# Volta-Interface-SCH_SH2__01.net
KiCad netlist of a schematic drawn in Altium Designer
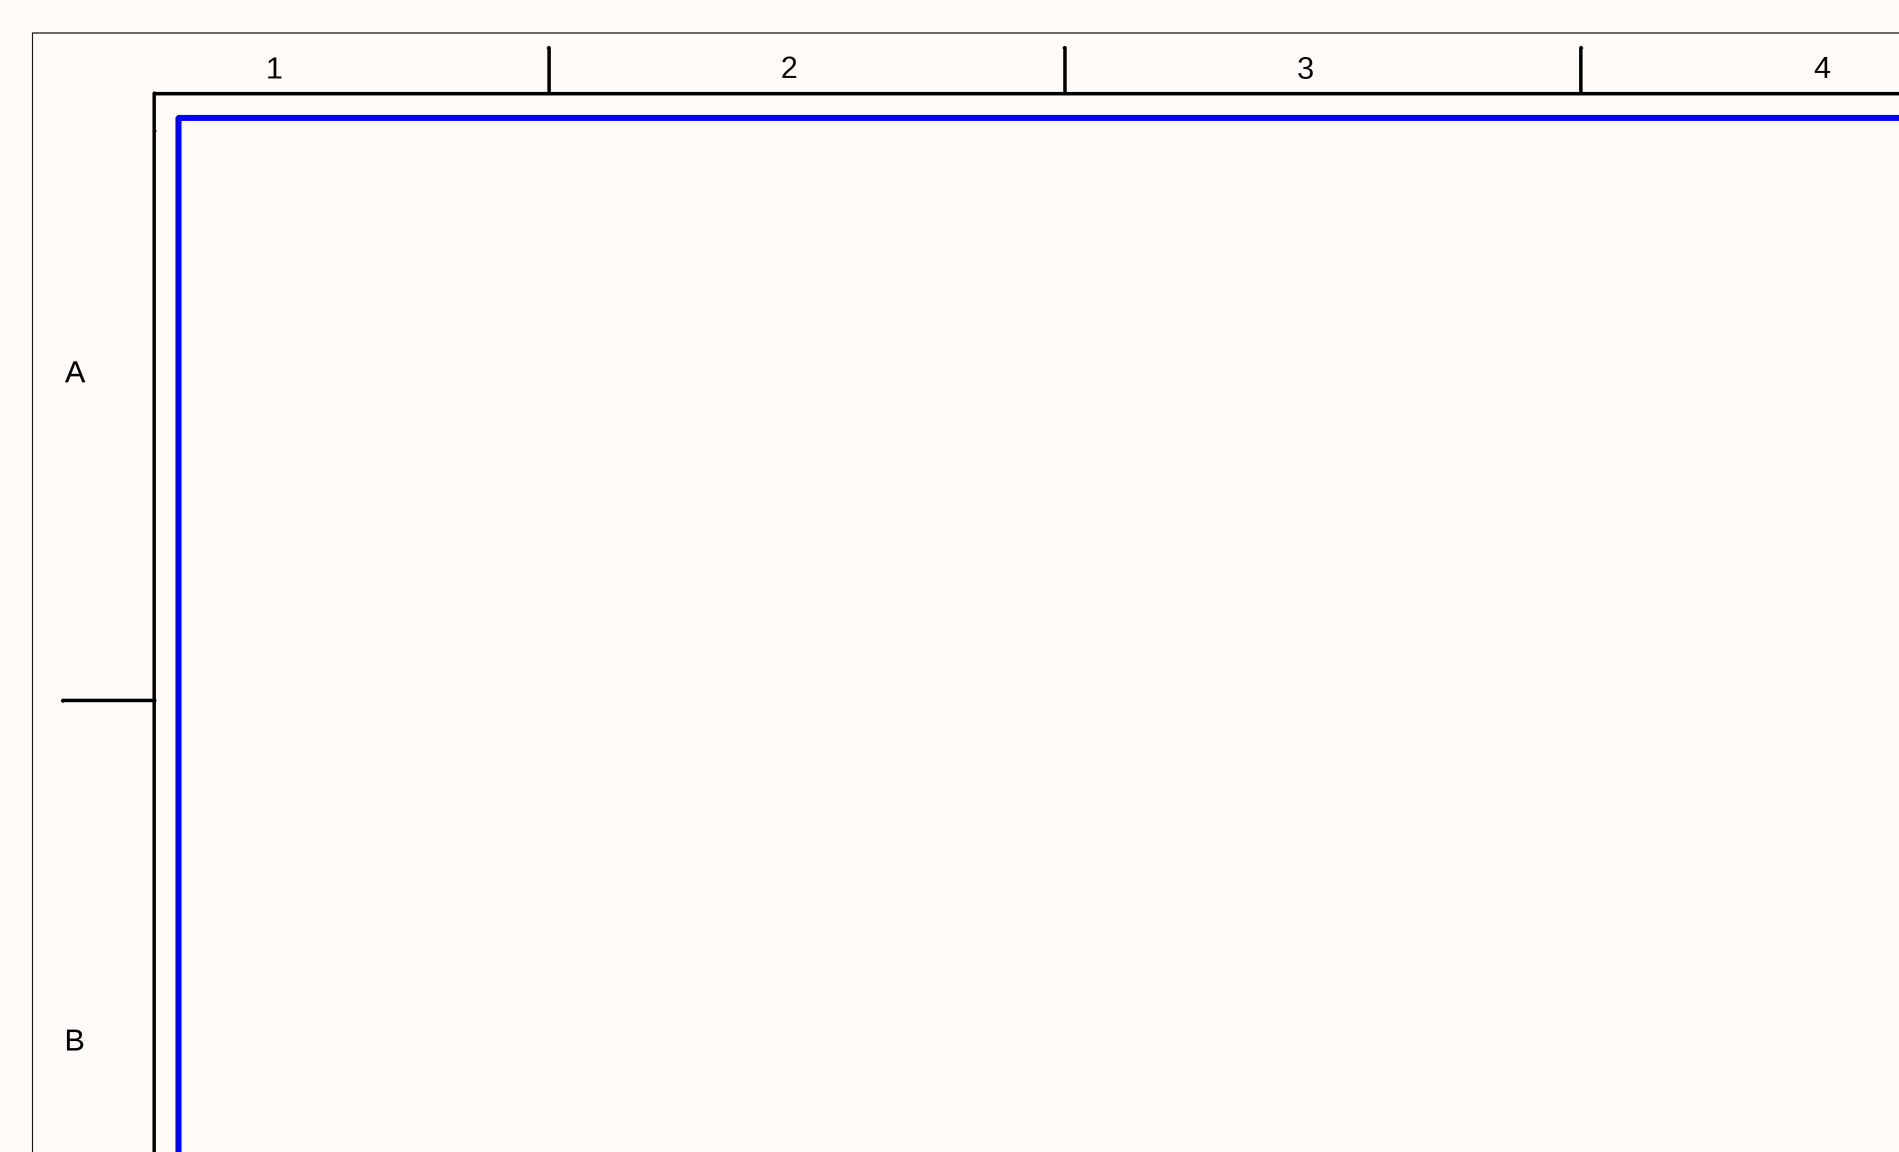
[diagram p0: Volta-Interface-SCH_SH2_(01).SchDoc, top left]
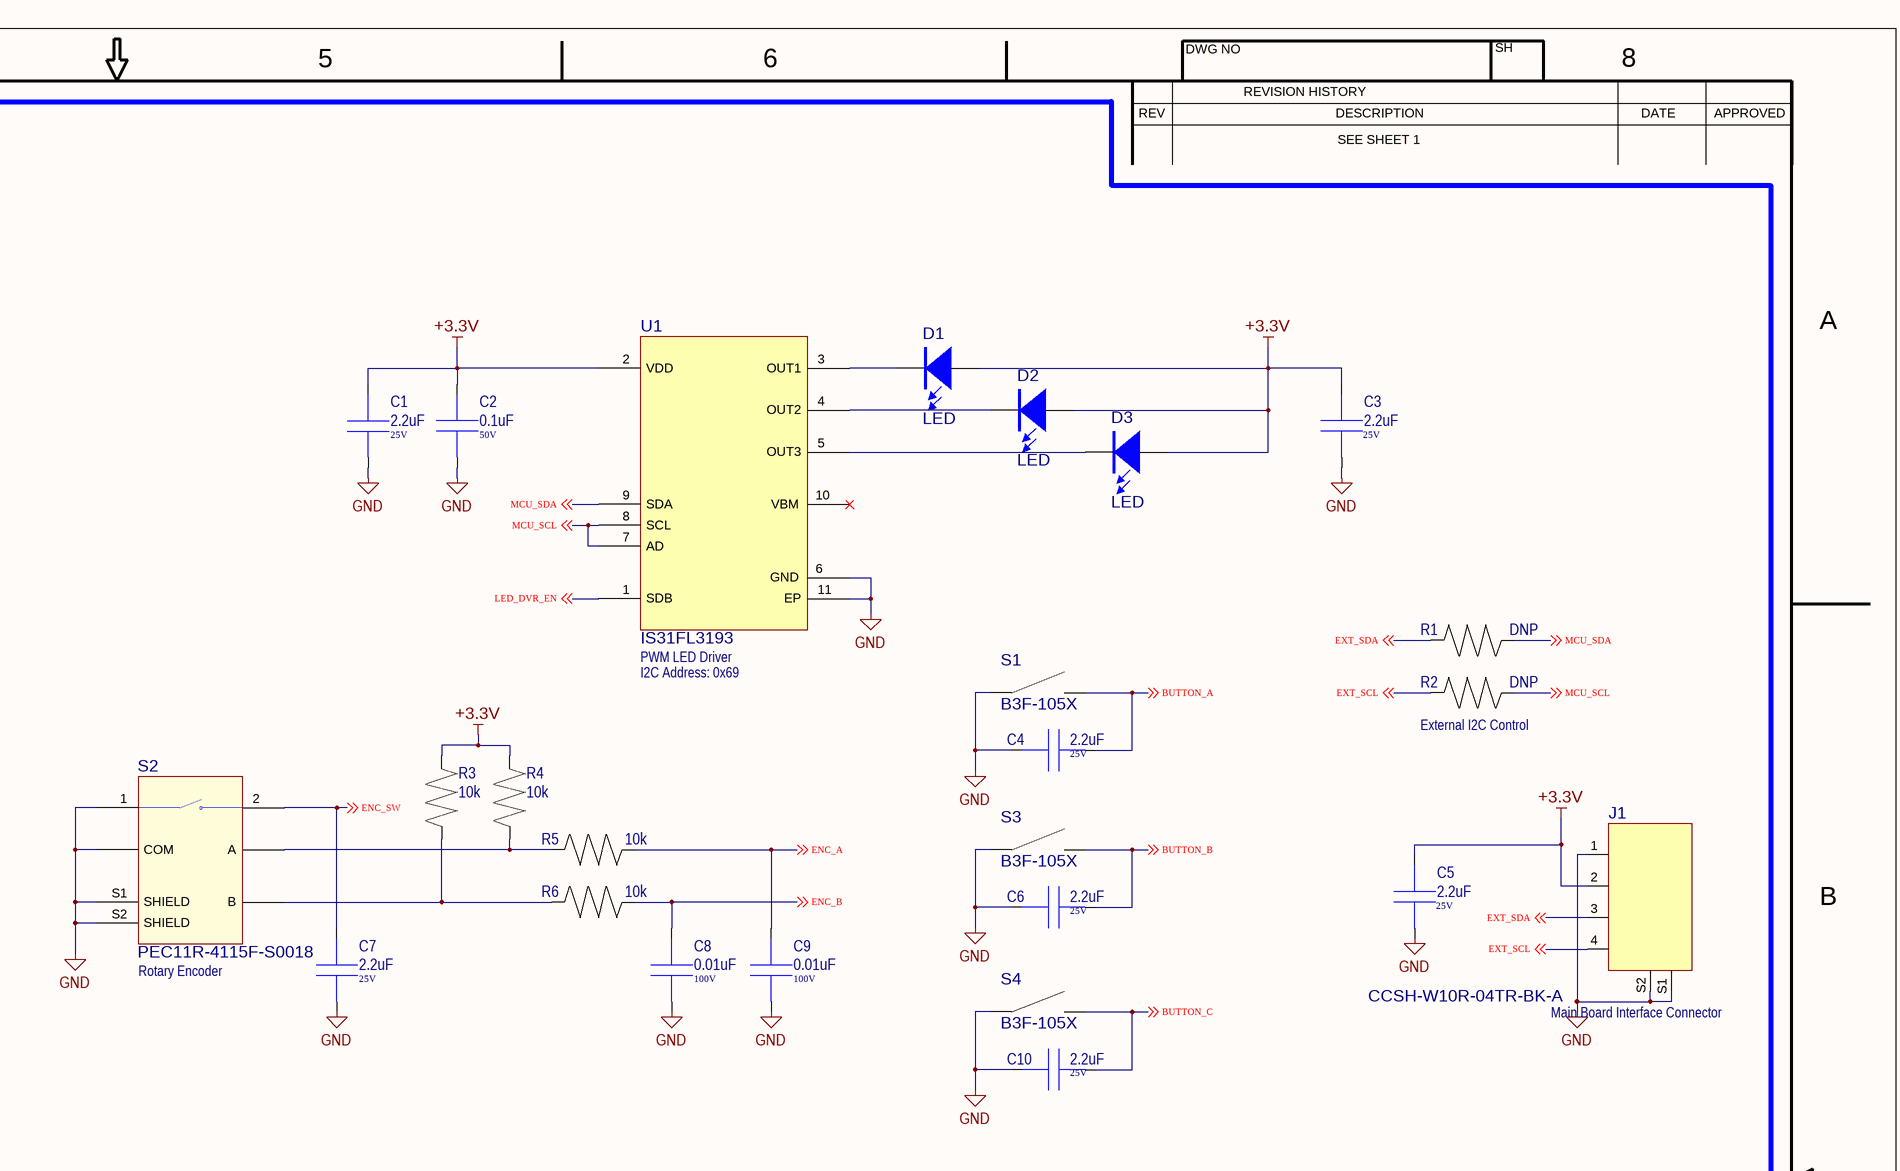
[diagram p1: Volta-Interface-SCH_SH2_(01).SchDoc, top right]
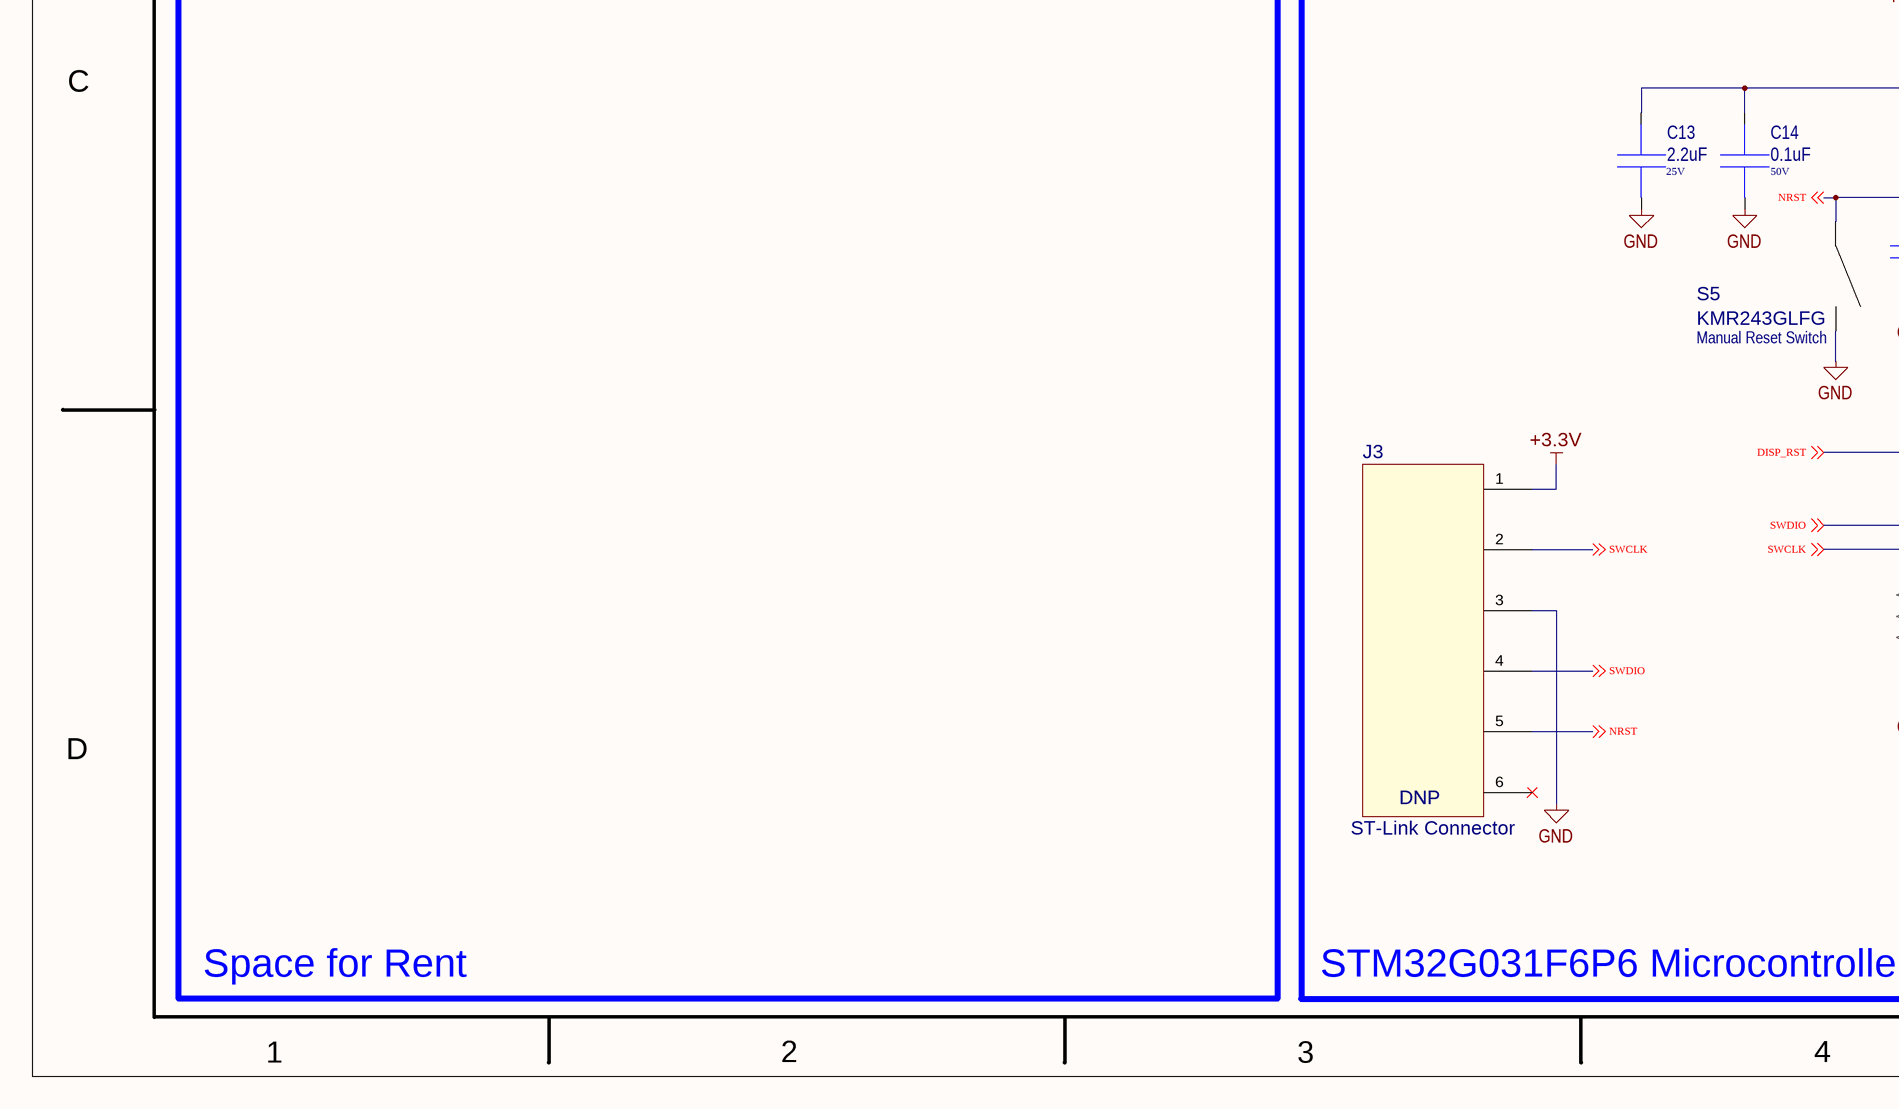
[diagram p2: Volta-Interface-SCH_SH2_(01).SchDoc, bottom left]
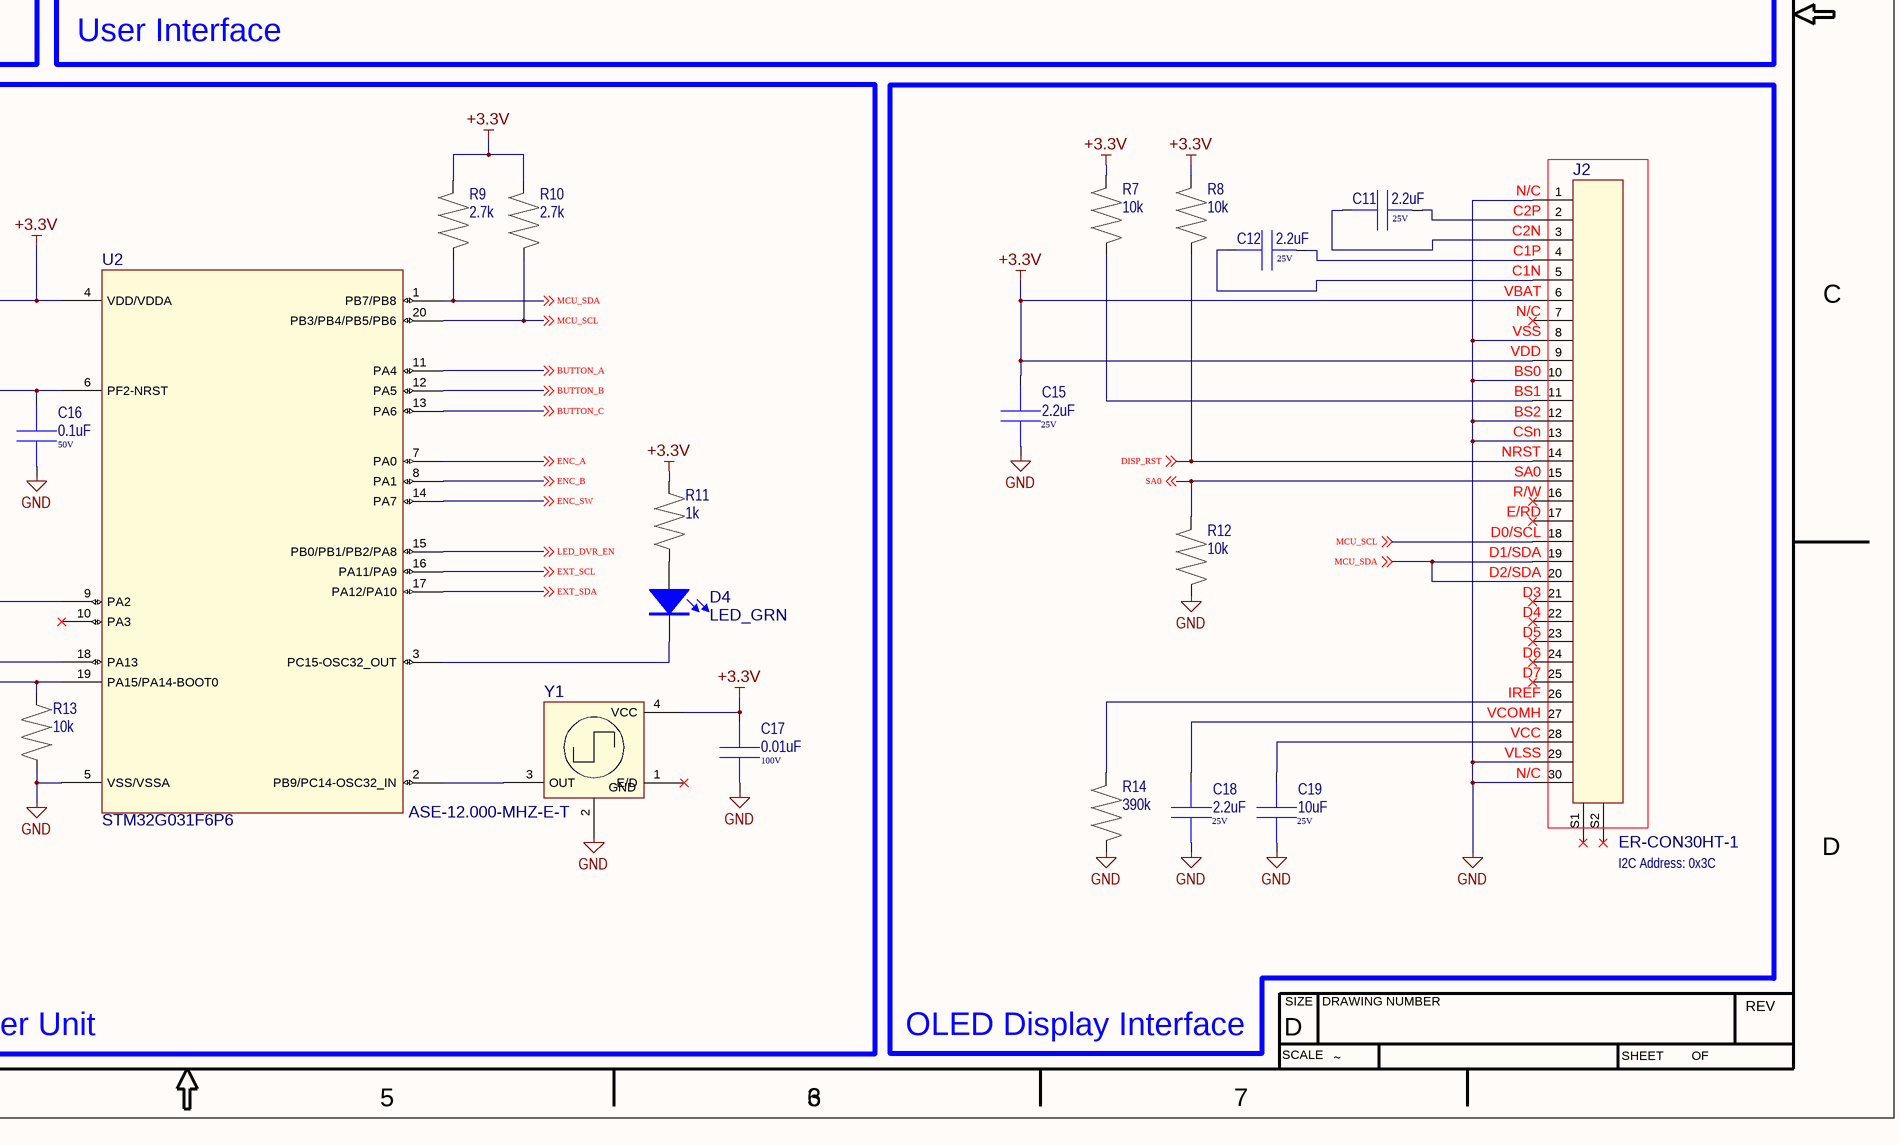
[diagram p3: Volta-Interface-SCH_SH2_(01).SchDoc, bottom right]

(export (version "E")
  (design (tool "Eeschema 10.0.6"))
  (components
    (comp (ref "C1")
      (value "2.2uF")
      (footprint "0402")
      (description "Multilayer Ceramic Capacitors MLCC - SMD/SMT 2.2UF 25V 10% 0402")
      (fields
        (field (name "PART NUMBER") "GRM155R61E225KE11D")
        (field (name "MANUFACTURER") "Murata Electronics")
        (field (name "VOLTAGE") "25V")
      )
      (libsource (lib "CAPACITORS") (part "CAP"))
    )
    (comp (ref "C2")
      (value "0.1uF")
      (footprint "0402")
      (description "CAP CER 0.1UF 50V X7R 0402")
      (fields
        (field (name "PART NUMBER") "UMK105B7104KVHF")
        (field (name "MANUFACTURER") "Taiyo Yuden")
        (field (name "VOLTAGE") "50V")
      )
      (libsource (lib "CAPACITORS") (part "CAP"))
    )
    (comp (ref "C3")
      (value "2.2uF")
      (footprint "0402")
      (description "Multilayer Ceramic Capacitors MLCC - SMD/SMT 2.2UF 25V 10% 0402")
      (fields
        (field (name "PART NUMBER") "GRM155R61E225KE11D")
        (field (name "MANUFACTURER") "Murata Electronics")
        (field (name "VOLTAGE") "25V")
      )
      (libsource (lib "CAPACITORS") (part "CAP"))
    )
    (comp (ref "C4")
      (value "2.2uF")
      (footprint "0402")
      (description "Multilayer Ceramic Capacitors MLCC - SMD/SMT 2.2UF 25V 10% 0402")
      (fields
        (field (name "PART NUMBER") "GRM155R61E225KE11D")
        (field (name "MANUFACTURER") "Murata Electronics")
        (field (name "VOLTAGE") "25V")
      )
      (libsource (lib "CAPACITORS") (part "CAP"))
    )
    (comp (ref "C5")
      (value "2.2uF")
      (footprint "0402")
      (description "Multilayer Ceramic Capacitors MLCC - SMD/SMT 2.2UF 25V 10% 0402")
      (fields
        (field (name "PART NUMBER") "GRM155R61E225KE11D")
        (field (name "MANUFACTURER") "Murata Electronics")
        (field (name "VOLTAGE") "25V")
      )
      (libsource (lib "CAPACITORS") (part "CAP"))
    )
    (comp (ref "C6")
      (value "2.2uF")
      (footprint "0402")
      (description "Multilayer Ceramic Capacitors MLCC - SMD/SMT 2.2UF 25V 10% 0402")
      (fields
        (field (name "PART NUMBER") "GRM155R61E225KE11D")
        (field (name "MANUFACTURER") "Murata Electronics")
        (field (name "VOLTAGE") "25V")
      )
      (libsource (lib "CAPACITORS") (part "CAP"))
    )
    (comp (ref "C7")
      (value "2.2uF")
      (footprint "0402")
      (description "Multilayer Ceramic Capacitors MLCC - SMD/SMT 2.2UF 25V 10% 0402")
      (fields
        (field (name "PART NUMBER") "GRM155R61E225KE11D")
        (field (name "MANUFACTURER") "Murata Electronics")
        (field (name "VOLTAGE") "25V")
      )
      (libsource (lib "CAPACITORS") (part "CAP"))
    )
    (comp (ref "C8")
      (value "0.01uF")
      (footprint "0402")
      (description "CAP CER 0.01UF 100V X7R 0402")
      (fields
        (field (name "PART NUMBER") "HMR105B7103MV-F")
        (field (name "MANUFACTURER") "Taiyo Yuden")
        (field (name "VOLTAGE") "100V")
      )
      (libsource (lib "CAPACITORS") (part "CAP"))
    )
    (comp (ref "C9")
      (value "0.01uF")
      (footprint "0402")
      (description "CAP CER 0.01UF 100V X7R 0402")
      (fields
        (field (name "PART NUMBER") "HMR105B7103MV-F")
        (field (name "MANUFACTURER") "Taiyo Yuden")
        (field (name "VOLTAGE") "100V")
      )
      (libsource (lib "CAPACITORS") (part "CAP"))
    )
    (comp (ref "C10")
      (value "2.2uF")
      (footprint "0402")
      (description "Multilayer Ceramic Capacitors MLCC - SMD/SMT 2.2UF 25V 10% 0402")
      (fields
        (field (name "PART NUMBER") "GRM155R61E225KE11D")
        (field (name "MANUFACTURER") "Murata Electronics")
        (field (name "VOLTAGE") "25V")
      )
      (libsource (lib "CAPACITORS") (part "CAP"))
    )
    (comp (ref "C11")
      (value "2.2uF")
      (footprint "0402")
      (description "CAP CER 10UF 10V X6S 0603")
      (fields
        (field (name "PART NUMBER") "GRM188C81A106MA73D")
        (field (name "MANUFACTURER") "Murata Electronics")
        (field (name "VOLTAGE") "25V")
      )
      (libsource (lib "CAPACITORS") (part "CAP"))
    )
    (comp (ref "C12")
      (value "2.2uF")
      (footprint "0402")
      (description "CAP CER 10UF 10V X6S 0603")
      (fields
        (field (name "PART NUMBER") "GRM188C81A106MA73D")
        (field (name "MANUFACTURER") "Murata Electronics")
        (field (name "VOLTAGE") "25V")
      )
      (libsource (lib "CAPACITORS") (part "CAP"))
    )
    (comp (ref "C13")
      (value "2.2uF")
      (footprint "0402")
      (description "Multilayer Ceramic Capacitors MLCC - SMD/SMT 2.2UF 25V 10% 0402")
      (fields
        (field (name "PART NUMBER") "GRM155R61E225KE11D")
        (field (name "MANUFACTURER") "Murata Electronics")
        (field (name "VOLTAGE") "25V")
      )
      (libsource (lib "CAPACITORS") (part "CAP"))
    )
    (comp (ref "C14")
      (value "0.1uF")
      (footprint "0402")
      (description "CAP CER 0.1UF 50V X7R 0402")
      (fields
        (field (name "PART NUMBER") "UMK105B7104KVHF")
        (field (name "MANUFACTURER") "Taiyo Yuden")
        (field (name "VOLTAGE") "50V")
      )
      (libsource (lib "CAPACITORS") (part "CAP"))
    )
    (comp (ref "C15")
      (value "2.2uF")
      (footprint "0402")
      (description "CAP CER 10UF 10V X6S 0603")
      (fields
        (field (name "PART NUMBER") "GRM188C81A106MA73D")
        (field (name "MANUFACTURER") "Murata Electronics")
        (field (name "VOLTAGE") "25V")
      )
      (libsource (lib "CAPACITORS") (part "CAP"))
    )
    (comp (ref "C16")
      (value "0.1uF")
      (footprint "0402")
      (description "CAP CER 0.1UF 50V X7R 0402")
      (fields
        (field (name "PART NUMBER") "UMK105B7104KVHF")
        (field (name "MANUFACTURER") "Taiyo Yuden")
        (field (name "VOLTAGE") "50V")
      )
      (libsource (lib "CAPACITORS") (part "CAP"))
    )
    (comp (ref "C17")
      (value "0.01uF")
      (footprint "0402")
      (description "CAP CER 0.01UF 100V X7R 0402")
      (fields
        (field (name "PART NUMBER") "HMR105B7103MV-F")
        (field (name "MANUFACTURER") "Taiyo Yuden")
        (field (name "VOLTAGE") "100V")
      )
      (libsource (lib "CAPACITORS") (part "CAP"))
    )
    (comp (ref "C18")
      (value "2.2uF")
      (footprint "0402")
      (description "CAP CER 10UF 10V X6S 0603")
      (fields
        (field (name "PART NUMBER") "GRM188C81A106MA73D")
        (field (name "MANUFACTURER") "Murata Electronics")
        (field (name "VOLTAGE") "25V")
      )
      (libsource (lib "CAPACITORS") (part "CAP"))
    )
    (comp (ref "C19")
      (value "10uF")
      (footprint "0402")
      (description "CAP CER 10UF 10V X6S 0603")
      (fields
        (field (name "PART NUMBER") "GRM188C81A106MA73D")
        (field (name "MANUFACTURER") "Murata Electronics")
        (field (name "VOLTAGE") "25V")
      )
      (libsource (lib "CAPACITORS") (part "CAP"))
    )
    (comp (ref "D1") (value "LED") (footprint "1206_LED") (libsource (lib "SEMICONDUCTORS") (part "LED")))
    (comp (ref "D2") (value "LED") (footprint "1206_LED") (libsource (lib "SEMICONDUCTORS") (part "LED")))
    (comp (ref "D3") (value "LED") (footprint "1206_LED") (libsource (lib "SEMICONDUCTORS") (part "LED")))
    (comp (ref "D4")
      (value "LED_GRN")
      (footprint "0603_LED_Red")
      (description "Standard LEDs - SMD HE Red 645 nm Water Clear")
      (fields (field (name "PART NUMBER") "SM0603HCL") (field (name "MANUFACTURER") "Bivar"))
      (libsource (lib "SEMICONDUCTORS") (part "LED_Red"))
    )
    (comp (ref "J1")
      (value "CCSH-W10R-04TR-BK-A")
      (footprint "PCBComponent_1")
      (fields (field (name "MANUFACTURER") "JST"))
      (libsource (lib "CCSH-W10R-04TR-BK-A") (part "CCSH-W10R-04TR-BK-A"))
    )
    (comp (ref "J2")
      (value "ER-CON30HT-1")
      (footprint "ER-CON30HT-1")
      (description "30 PINS 0.5 PITCH SMD TOP CONTACT CONN")
      (fields (field (name "MANUFACTURER") "EastRising Technology"))
      (libsource (lib "ER-CON30HT-1") (part "ER-CON30HT-1"))
    )
    (comp (ref "J3")
      (value "DNP")
      (footprint "801-93-006-10-012000")
      (description "CONN SOCKET STRIP LOPRO 6POS")
      (fields (field (name "MANUFACTURER") "Mill-Max") (field (name "PART NUMBER") "801-93-006-10-012000"))
      (libsource (lib "Connectors") (part "801-93-006-10-012000"))
    )
    (comp (ref "R1")
      (value "DNP")
      (footprint "0402")
      (description "Thick Film Resistors - SMD 1/16watt 0ohm Commercial Use")
      (fields (field (name "PART NUMBER") "CRCW04020000Z0EDC") (field (name "MANUFACTURER") "Vishay / Dale"))
      (libsource (lib "RESISTORS") (part "RES"))
    )
    (comp (ref "R2")
      (value "DNP")
      (footprint "0402")
      (description "Thick Film Resistors - SMD 1/16watt 0ohm Commercial Use")
      (fields (field (name "PART NUMBER") "CRCW04020000Z0EDC") (field (name "MANUFACTURER") "Vishay / Dale"))
      (libsource (lib "RESISTORS") (part "RES"))
    )
    (comp (ref "R3")
      (value "10k")
      (footprint "0402")
      (description "Thick Film Resistors - SMD 10K OHM 1%")
      (fields (field (name "PART NUMBER") "CR0402-FX-1002GLF") (field (name "MANUFACTURER") "Bourns"))
      (libsource (lib "RESISTORS") (part "RES"))
    )
    (comp (ref "R4")
      (value "10k")
      (footprint "0402")
      (description "Thick Film Resistors - SMD 10K OHM 1%")
      (fields (field (name "PART NUMBER") "CR0402-FX-1002GLF") (field (name "MANUFACTURER") "Bourns"))
      (libsource (lib "RESISTORS") (part "RES"))
    )
    (comp (ref "R5")
      (value "10k")
      (footprint "0402")
      (description "Thick Film Resistors - SMD 10K OHM 1%")
      (fields (field (name "PART NUMBER") "CR0402-FX-1002GLF") (field (name "MANUFACTURER") "Bourns"))
      (libsource (lib "RESISTORS") (part "RES"))
    )
    (comp (ref "R6")
      (value "10k")
      (footprint "0402")
      (description "Thick Film Resistors - SMD 10K OHM 1%")
      (fields (field (name "PART NUMBER") "CR0402-FX-1002GLF") (field (name "MANUFACTURER") "Bourns"))
      (libsource (lib "RESISTORS") (part "RES"))
    )
    (comp (ref "R7")
      (value "10k")
      (footprint "0402")
      (description "Thick Film Resistors - SMD 0603 5.1Kohm 5% High Voltage")
      (fields (field (name "PART NUMBER") "KTR03EZPJ512") (field (name "MANUFACTURER") "ROHM Semiconductor"))
      (libsource (lib "RESISTORS") (part "RES"))
    )
    (comp (ref "R8")
      (value "10k")
      (footprint "0402")
      (description "Thick Film Resistors - SMD 0603 5.1Kohm 5% High Voltage")
      (fields (field (name "PART NUMBER") "KTR03EZPJ512") (field (name "MANUFACTURER") "ROHM Semiconductor"))
      (libsource (lib "RESISTORS") (part "RES"))
    )
    (comp (ref "R9")
      (value "2.7k")
      (footprint "0402")
      (description "Thick Film Resistors - SMD 0402 2.7Kohms 1% AEC-Q200")
      (fields (field (name "PART NUMBER") "ERJ-2RKF2701X") (field (name "MANUFACTURER") "Panasonic"))
      (libsource (lib "RESISTORS") (part "RES"))
    )
    (comp (ref "R10")
      (value "2.7k")
      (footprint "0402")
      (description "Thick Film Resistors - SMD 0402 2.7Kohms 1% AEC-Q200")
      (fields (field (name "PART NUMBER") "ERJ-2RKF2701X") (field (name "MANUFACTURER") "Panasonic"))
      (libsource (lib "RESISTORS") (part "RES"))
    )
    (comp (ref "R11")
      (value "1k")
      (footprint "0402")
      (description "Thick Film Resistors - SMD ResA 0402 1k 1% 63mW TC100")
      (fields (field (name "PART NUMBER") "CR0402AFX-1001GLF") (field (name "MANUFACTURER") "Bourns"))
      (libsource (lib "RESISTORS") (part "RES"))
    )
    (comp (ref "R12")
      (value "10k")
      (footprint "0402")
      (description "Thick Film Resistors - SMD 0603 5.1Kohm 5% High Voltage")
      (fields (field (name "PART NUMBER") "KTR03EZPJ512") (field (name "MANUFACTURER") "ROHM Semiconductor"))
      (libsource (lib "RESISTORS") (part "RES"))
    )
    (comp (ref "R13")
      (value "10k")
      (footprint "0402")
      (description "Thick Film Resistors - SMD 10K OHM 1%")
      (fields (field (name "PART NUMBER") "CR0402-FX-1002GLF") (field (name "MANUFACTURER") "Bourns"))
      (libsource (lib "RESISTORS") (part "RES"))
    )
    (comp (ref "R14")
      (value "390k")
      (footprint "0402")
      (description "Thick Film Resistors - SMD 0603 5.1Kohm 5% High Voltage")
      (fields (field (name "PART NUMBER") "KTR03EZPJ512") (field (name "MANUFACTURER") "ROHM Semiconductor"))
      (libsource (lib "RESISTORS") (part "RES"))
    )
    (comp (ref "S1")
      (value "B3F-105X")
      (footprint "B3F-105X")
      (description "SWITCH TACTILE SPST-NO 0.05A 24V")
      (fields (field (name "MANUFACTURER") "Omron Electronics Inc-EMC Div"))
      (libsource (lib "B3F-105X") (part "B3F-105X"))
    )
    (comp (ref "S2")
      (value "PEC11R-4115F-S0018")
      (footprint "PEC11R-4xxxF-Sxxxx")
      (description "ROTARY ENCODER MECHANICAL XXPPR")
      (fields (field (name "MANUFACTURER") "Bourns"))
      (libsource (lib "PEC11R-4xxxF-Sxxxx") (part "PEC11R-4xxxF-Sxxxx"))
    )
    (comp (ref "S3")
      (value "B3F-105X")
      (footprint "B3F-105X")
      (description "SWITCH TACTILE SPST-NO 0.05A 24V")
      (fields (field (name "MANUFACTURER") "Omron Electronics Inc-EMC Div"))
      (libsource (lib "B3F-105X") (part "B3F-105X"))
    )
    (comp (ref "S4")
      (value "B3F-105X")
      (footprint "B3F-105X")
      (description "SWITCH TACTILE SPST-NO 0.05A 24V")
      (fields (field (name "MANUFACTURER") "Omron Electronics Inc-EMC Div"))
      (libsource (lib "B3F-105X") (part "B3F-105X"))
    )
    (comp (ref "S5")
      (value "KMR243GLFG")
      (footprint "KMR 2 Series")
      (description "Tactile Switch SPST-NO Top Actuated Surface Mount")
      (fields (field (name "MANUFACTURER") "C&K") (field (name "PART NUMBER") "KMR243GFLG"))
      (libsource (lib "KMR2 Series") (part "KMR 2 Series"))
    )
    (comp (ref "U1")
      (value "IS31FL3193")
      (footprint "DFN-10")
      (description "IC LED DRIVER LINEAR 42MA 10DFN")
      (fields
        (field (name "MANUFACTURER") "Lumissil Microsystems")
        (field (name "PART NUMBER") "IS31FL3193-DLS2-TR")
      )
      (libsource (lib "IS31FL3193") (part "IS31FL3193"))
    )
    (comp (ref "U2")
      (value "STM32G031F6P6")
      (footprint "TSSOP-20")
      (description "IC MCU 32BIT 32KB FLASH 20TSSOP")
      (fields (field (name "MANUFACTURER") "STMicroelectronics"))
      (libsource (lib "STM32G031Fxxx") (part "STM32G031F6P6"))
    )
    (comp (ref "Y1")
      (value "ASE-12.000-MHZ-E-T")
      (footprint "ASE-XXXXX-X-X-X")
      (description "OSC XO 12.000MHZ CMOS SMD")
      (fields (field (name "MANUFACTURER") "Abracon"))
      (libsource (lib "Oscillators") (part "ASE-XXXXX-MHZ-X-X"))
    )
  )
  (nets
    (net (code "1") (name "+3.3V") (class "Default")
      (node (ref "C1") (pin "2") (pinfunction "2_2") (pintype "passive"))
      (node (ref "C13") (pin "2") (pinfunction "2_2") (pintype "passive"))
      (node (ref "C14") (pin "2") (pinfunction "2_2") (pintype "passive"))
      (node (ref "C15") (pin "2") (pinfunction "2_2") (pintype "passive"))
      (node (ref "C17") (pin "2") (pinfunction "2_2") (pintype "passive"))
      (node (ref "C2") (pin "2") (pinfunction "2_2") (pintype "passive"))
      (node (ref "C3") (pin "2") (pinfunction "2_2") (pintype "passive"))
      (node (ref "C5") (pin "2") (pinfunction "2_2") (pintype "passive"))
      (node (ref "D1") (pin "1") (pinfunction "A_1") (pintype "passive"))
      (node (ref "D2") (pin "1") (pinfunction "A_1") (pintype "passive"))
      (node (ref "D3") (pin "1") (pinfunction "A_1") (pintype "passive"))
      (node (ref "J1") (pin "2") (pinfunction "2_2") (pintype "passive"))
      (node (ref "J2") (pin "6") (pinfunction "6_6") (pintype "passive"))
      (node (ref "J2") (pin "9") (pinfunction "9_9") (pintype "passive"))
      (node (ref "J3") (pin "1") (pinfunction "1_1") (pintype "passive"))
      (node (ref "R10") (pin "2") (pinfunction "2_2") (pintype "passive"))
      (node (ref "R11") (pin "2") (pinfunction "2_2") (pintype "passive"))
      (node (ref "R3") (pin "1") (pinfunction "1_1") (pintype "passive"))
      (node (ref "R4") (pin "1") (pinfunction "1_1") (pintype "passive"))
      (node (ref "R7") (pin "2") (pinfunction "2_2") (pintype "passive"))
      (node (ref "R8") (pin "2") (pinfunction "2_2") (pintype "passive"))
      (node (ref "R9") (pin "2") (pinfunction "2_2") (pintype "passive"))
      (node (ref "U1") (pin "2") (pinfunction "VDD_2") (pintype "passive"))
      (node (ref "U2") (pin "4") (pinfunction "VDD/VDDA_4") (pintype "power_in"))
      (node (ref "Y1") (pin "4") (pinfunction "VCC_4") (pintype "power_in"))
    )
    (net (code "2") (name "BUTTON_A") (class "Default")
      (node (ref "C4") (pin "1") (pinfunction "1_1") (pintype "passive"))
      (node (ref "S1") (pin "2") (pinfunction "2_2") (pintype "passive"))
      (node (ref "U2") (pin "11") (pinfunction "PA4_11") (pintype "bidirectional"))
    )
    (net (code "3") (name "BUTTON_B") (class "Default")
      (node (ref "C6") (pin "1") (pinfunction "1_1") (pintype "passive"))
      (node (ref "S3") (pin "2") (pinfunction "2_2") (pintype "passive"))
      (node (ref "U2") (pin "12") (pinfunction "PA5_12") (pintype "bidirectional"))
    )
    (net (code "4") (name "BUTTON_C") (class "Default")
      (node (ref "C10") (pin "1") (pinfunction "1_1") (pintype "passive"))
      (node (ref "S4") (pin "2") (pinfunction "2_2") (pintype "passive"))
      (node (ref "U2") (pin "13") (pinfunction "PA6_13") (pintype "bidirectional"))
    )
    (net (code "5") (name "DISP_RST") (class "Default")
      (node (ref "J2") (pin "14") (pinfunction "14_14") (pintype "passive"))
      (node (ref "R8") (pin "1") (pinfunction "1_1") (pintype "passive"))
      (node (ref "U2") (pin "9") (pinfunction "PA2_9") (pintype "bidirectional"))
    )
    (net (code "6") (name "ENC_A") (class "Default")
      (node (ref "C9") (pin "2") (pinfunction "2_2") (pintype "passive"))
      (node (ref "R5") (pin "2") (pinfunction "2_2") (pintype "passive"))
      (node (ref "U2") (pin "7") (pinfunction "PA0_7") (pintype "bidirectional"))
    )
    (net (code "7") (name "ENC_B") (class "Default")
      (node (ref "C8") (pin "2") (pinfunction "2_2") (pintype "passive"))
      (node (ref "R6") (pin "2") (pinfunction "2_2") (pintype "passive"))
      (node (ref "U2") (pin "8") (pinfunction "PA1_8") (pintype "bidirectional"))
    )
    (net (code "8") (name "ENC_SW") (class "Default")
      (node (ref "C7") (pin "2") (pinfunction "2_2") (pintype "passive"))
      (node (ref "S2") (pin "2") (pinfunction "2_2") (pintype "passive"))
      (node (ref "U2") (pin "14") (pinfunction "PA7_14") (pintype "bidirectional"))
    )
    (net (code "9") (name "EXT_SCL") (class "Default")
      (node (ref "J1") (pin "4") (pinfunction "4_4") (pintype "passive"))
      (node (ref "R2") (pin "2") (pinfunction "2_2") (pintype "passive"))
      (node (ref "U2") (pin "16") (pinfunction "PA11/PA9_16") (pintype "bidirectional"))
    )
    (net (code "10") (name "EXT_SDA") (class "Default")
      (node (ref "J1") (pin "3") (pinfunction "3_3") (pintype "passive"))
      (node (ref "R1") (pin "2") (pinfunction "2_2") (pintype "passive"))
      (node (ref "U2") (pin "17") (pinfunction "PA12/PA10_17") (pintype "bidirectional"))
    )
    (net (code "11") (name "GND") (class "Default")
      (node (ref "C1") (pin "1") (pinfunction "1_1") (pintype "passive"))
      (node (ref "C10") (pin "2") (pinfunction "2_2") (pintype "passive"))
      (node (ref "C13") (pin "1") (pinfunction "1_1") (pintype "passive"))
      (node (ref "C14") (pin "1") (pinfunction "1_1") (pintype "passive"))
      (node (ref "C15") (pin "1") (pinfunction "1_1") (pintype "passive"))
      (node (ref "C16") (pin "1") (pinfunction "1_1") (pintype "passive"))
      (node (ref "C17") (pin "1") (pinfunction "1_1") (pintype "passive"))
      (node (ref "C18") (pin "1") (pinfunction "1_1") (pintype "passive"))
      (node (ref "C19") (pin "1") (pinfunction "1_1") (pintype "passive"))
      (node (ref "C2") (pin "1") (pinfunction "1_1") (pintype "passive"))
      (node (ref "C3") (pin "1") (pinfunction "1_1") (pintype "passive"))
      (node (ref "C4") (pin "2") (pinfunction "2_2") (pintype "passive"))
      (node (ref "C5") (pin "1") (pinfunction "1_1") (pintype "passive"))
      (node (ref "C6") (pin "2") (pinfunction "2_2") (pintype "passive"))
      (node (ref "C7") (pin "1") (pinfunction "1_1") (pintype "passive"))
      (node (ref "C8") (pin "1") (pinfunction "1_1") (pintype "passive"))
      (node (ref "C9") (pin "1") (pinfunction "1_1") (pintype "passive"))
      (node (ref "J1") (pin "1") (pinfunction "1_1") (pintype "passive"))
      (node (ref "J1") (pin "S1") (pinfunction "S1_S1") (pintype "passive"))
      (node (ref "J1") (pin "S2") (pinfunction "S2_S2") (pintype "passive"))
      (node (ref "J2") (pin "1") (pinfunction "1_1") (pintype "passive"))
      (node (ref "J2") (pin "10") (pinfunction "10_10") (pintype "passive"))
      (node (ref "J2") (pin "12") (pinfunction "12_12") (pintype "passive"))
      (node (ref "J2") (pin "13") (pinfunction "13_13") (pintype "passive"))
      (node (ref "J2") (pin "29") (pinfunction "29_29") (pintype "passive"))
      (node (ref "J2") (pin "30") (pinfunction "30_30") (pintype "passive"))
      (node (ref "J2") (pin "8") (pinfunction "8_8") (pintype "passive"))
      (node (ref "J3") (pin "3") (pinfunction "3_3") (pintype "passive"))
      (node (ref "R12") (pin "1") (pinfunction "1_1") (pintype "passive"))
      (node (ref "R13") (pin "2") (pinfunction "2_2") (pintype "passive"))
      (node (ref "R14") (pin "1") (pinfunction "1_1") (pintype "passive"))
      (node (ref "S1") (pin "1") (pinfunction "1_1") (pintype "passive"))
      (node (ref "S2") (pin "1") (pinfunction "1_1") (pintype "passive"))
      (node (ref "S2") (pin "COM") (pinfunction "COM_COM") (pintype "passive"))
      (node (ref "S2") (pin "S1") (pinfunction "SHIELD_S1") (pintype "passive"))
      (node (ref "S2") (pin "S2") (pinfunction "SHIELD_S2") (pintype "passive"))
      (node (ref "S3") (pin "1") (pinfunction "1_1") (pintype "passive"))
      (node (ref "S4") (pin "1") (pinfunction "1_1") (pintype "passive"))
      (node (ref "S5") (pin "2") (pinfunction "2_2") (pintype "passive"))
      (node (ref "U1") (pin "11") (pinfunction "EP_11") (pintype "passive"))
      (node (ref "U1") (pin "6") (pinfunction "GND_6") (pintype "passive"))
      (node (ref "U2") (pin "5") (pinfunction "VSS/VSSA_5") (pintype "power_in"))
      (node (ref "Y1") (pin "2") (pinfunction "GND_2") (pintype "passive"))
    )
    (net (code "12") (name "LED_DVR_EN") (class "Default")
      (node (ref "U1") (pin "1") (pinfunction "SDB_1") (pintype "passive"))
      (node (ref "U2") (pin "15") (pinfunction "PB0/PB1/PB2/PA8_15") (pintype "bidirectional"))
    )
    (net (code "13") (name "MCU_SCL") (class "Default")
      (node (ref "J2") (pin "18") (pinfunction "18_18") (pintype "passive"))
      (node (ref "R10") (pin "1") (pinfunction "1_1") (pintype "passive"))
      (node (ref "R2") (pin "1") (pinfunction "1_1") (pintype "passive"))
      (node (ref "U1") (pin "7") (pinfunction "AD_7") (pintype "passive"))
      (node (ref "U1") (pin "8") (pinfunction "SCL_8") (pintype "passive"))
      (node (ref "U2") (pin "20") (pinfunction "PB3/PB4/PB5/PB6_20") (pintype "bidirectional"))
    )
    (net (code "14") (name "MCU_SDA") (class "Default")
      (node (ref "J2") (pin "19") (pinfunction "19_19") (pintype "passive"))
      (node (ref "J2") (pin "20") (pinfunction "20_20") (pintype "passive"))
      (node (ref "R1") (pin "1") (pinfunction "1_1") (pintype "passive"))
      (node (ref "R9") (pin "1") (pinfunction "1_1") (pintype "passive"))
      (node (ref "U1") (pin "9") (pinfunction "SDA_9") (pintype "passive"))
      (node (ref "U2") (pin "1") (pinfunction "PB7/PB8_1") (pintype "bidirectional"))
    )
    (net (code "15") (name "NRST") (class "Default")
      (node (ref "C16") (pin "2") (pinfunction "2_2") (pintype "passive"))
      (node (ref "J3") (pin "5") (pinfunction "5_5") (pintype "passive"))
      (node (ref "S5") (pin "1") (pinfunction "1_1") (pintype "passive"))
      (node (ref "U2") (pin "6") (pinfunction "PF2-NRST_6") (pintype "passive"))
    )
    (net (code "16") (name "Net-(C11-Pad1)") (class "Default")
      (node (ref "C11") (pin "1") (pinfunction "1_1") (pintype "passive"))
      (node (ref "J2") (pin "2") (pinfunction "2_2") (pintype "passive"))
    )
    (net (code "17") (name "Net-(C11-Pad2)") (class "Default")
      (node (ref "C11") (pin "2") (pinfunction "2_2") (pintype "passive"))
      (node (ref "J2") (pin "3") (pinfunction "3_3") (pintype "passive"))
    )
    (net (code "18") (name "Net-(C12-Pad1)") (class "Default")
      (node (ref "C12") (pin "1") (pinfunction "1_1") (pintype "passive"))
      (node (ref "J2") (pin "4") (pinfunction "4_4") (pintype "passive"))
    )
    (net (code "19") (name "Net-(C12-Pad2)") (class "Default")
      (node (ref "C12") (pin "2") (pinfunction "2_2") (pintype "passive"))
      (node (ref "J2") (pin "5") (pinfunction "5_5") (pintype "passive"))
    )
    (net (code "20") (name "Net-(C18-Pad2)") (class "Default")
      (node (ref "C18") (pin "2") (pinfunction "2_2") (pintype "passive"))
      (node (ref "J2") (pin "27") (pinfunction "27_27") (pintype "passive"))
    )
    (net (code "21") (name "Net-(C19-Pad2)") (class "Default")
      (node (ref "C19") (pin "2") (pinfunction "2_2") (pintype "passive"))
      (node (ref "J2") (pin "28") (pinfunction "28_28") (pintype "passive"))
    )
    (net (code "22") (name "Net-(D1-K)") (class "Default")
      (node (ref "D1") (pin "2") (pinfunction "K_2") (pintype "passive"))
      (node (ref "U1") (pin "3") (pinfunction "OUT1_3") (pintype "passive"))
    )
    (net (code "23") (name "Net-(D2-K)") (class "Default")
      (node (ref "D2") (pin "2") (pinfunction "K_2") (pintype "passive"))
      (node (ref "U1") (pin "4") (pinfunction "OUT2_4") (pintype "passive"))
    )
    (net (code "24") (name "Net-(D3-K)") (class "Default")
      (node (ref "D3") (pin "2") (pinfunction "K_2") (pintype "passive"))
      (node (ref "U1") (pin "5") (pinfunction "OUT3_5") (pintype "passive"))
    )
    (net (code "25") (name "Net-(D4-A)") (class "Default")
      (node (ref "D4") (pin "1") (pinfunction "A_1") (pintype "passive"))
      (node (ref "R11") (pin "1") (pinfunction "1_1") (pintype "passive"))
    )
    (net (code "26") (name "Net-(D4-K)") (class "Default")
      (node (ref "D4") (pin "2") (pinfunction "K_2") (pintype "passive"))
      (node (ref "U2") (pin "3") (pinfunction "PC15-OSC32_OUT_3") (pintype "bidirectional"))
    )
    (net (code "27") (name "Net-(J2-Pad11)") (class "Default")
      (node (ref "J2") (pin "11") (pinfunction "11_11") (pintype "passive"))
      (node (ref "R7") (pin "1") (pinfunction "1_1") (pintype "passive"))
    )
    (net (code "28") (name "Net-(J2-Pad26)") (class "Default")
      (node (ref "J2") (pin "26") (pinfunction "26_26") (pintype "passive"))
      (node (ref "R14") (pin "2") (pinfunction "2_2") (pintype "passive"))
    )
    (net (code "29") (name "Net-(R3-Pad2)") (class "Default")
      (node (ref "R3") (pin "2") (pinfunction "2_2") (pintype "passive"))
      (node (ref "R6") (pin "1") (pinfunction "1_1") (pintype "passive"))
      (node (ref "S2") (pin "B") (pinfunction "B_B") (pintype "passive"))
    )
    (net (code "30") (name "Net-(R4-Pad2)") (class "Default")
      (node (ref "R4") (pin "2") (pinfunction "2_2") (pintype "passive"))
      (node (ref "R5") (pin "1") (pinfunction "1_1") (pintype "passive"))
      (node (ref "S2") (pin "A") (pinfunction "A_A") (pintype "passive"))
    )
    (net (code "31") (name "Net-(U2-PB9{slash}PC14-OSC32_IN)") (class "Default")
      (node (ref "U2") (pin "2") (pinfunction "PB9/PC14-OSC32_IN_2") (pintype "bidirectional"))
      (node (ref "Y1") (pin "3") (pinfunction "OUT_3") (pintype "passive"))
    )
    (net (code "32") (name "SA0") (class "Default")
      (node (ref "J2") (pin "15") (pinfunction "15_15") (pintype "passive"))
      (node (ref "R12") (pin "2") (pinfunction "2_2") (pintype "passive"))
    )
    (net (code "33") (name "SWCLK") (class "Default")
      (node (ref "J3") (pin "2") (pinfunction "2_2") (pintype "passive"))
      (node (ref "R13") (pin "1") (pinfunction "1_1") (pintype "passive"))
      (node (ref "U2") (pin "19") (pinfunction "PA15/PA14-BOOT0_19") (pintype "passive"))
    )
    (net (code "34") (name "SWDIO") (class "Default")
      (node (ref "J3") (pin "4") (pinfunction "4_4") (pintype "passive"))
      (node (ref "U2") (pin "18") (pinfunction "PA13_18") (pintype "bidirectional"))
    )
    (net (code "35") (name "unconnected-(J2-Pad7)") (class "Default")
      (node (ref "J2") (pin "7") (pinfunction "7_7") (pintype "passive+no_connect"))
    )
    (net (code "36") (name "unconnected-(J2-Pad16)") (class "Default")
      (node (ref "J2") (pin "16") (pinfunction "16_16") (pintype "passive+no_connect"))
    )
    (net (code "37") (name "unconnected-(J2-Pad17)") (class "Default")
      (node (ref "J2") (pin "17") (pinfunction "17_17") (pintype "passive+no_connect"))
    )
    (net (code "38") (name "unconnected-(J2-Pad21)") (class "Default")
      (node (ref "J2") (pin "21") (pinfunction "21_21") (pintype "passive+no_connect"))
    )
    (net (code "39") (name "unconnected-(J2-Pad22)") (class "Default")
      (node (ref "J2") (pin "22") (pinfunction "22_22") (pintype "passive+no_connect"))
    )
    (net (code "40") (name "unconnected-(J2-Pad23)") (class "Default")
      (node (ref "J2") (pin "23") (pinfunction "23_23") (pintype "passive+no_connect"))
    )
    (net (code "41") (name "unconnected-(J2-Pad24)") (class "Default")
      (node (ref "J2") (pin "24") (pinfunction "24_24") (pintype "passive+no_connect"))
    )
    (net (code "42") (name "unconnected-(J2-Pad25)") (class "Default")
      (node (ref "J2") (pin "25") (pinfunction "25_25") (pintype "passive+no_connect"))
    )
    (net (code "43") (name "unconnected-(J2-PadS1)") (class "Default")
      (node (ref "J2") (pin "S1") (pinfunction "S1_S1") (pintype "passive+no_connect"))
    )
    (net (code "44") (name "unconnected-(J2-PadS2)") (class "Default")
      (node (ref "J2") (pin "S2") (pinfunction "S2_S2") (pintype "passive+no_connect"))
    )
    (net (code "45") (name "unconnected-(J3-Pad6)") (class "Default")
      (node (ref "J3") (pin "6") (pinfunction "6_6") (pintype "passive+no_connect"))
    )
    (net (code "46") (name "unconnected-(U1-VBM-Pad10)") (class "Default")
      (node (ref "U1") (pin "10") (pinfunction "VBM_10") (pintype "passive+no_connect"))
    )
    (net (code "47") (name "unconnected-(U2-PA3-Pad10)") (class "Default")
      (node (ref "U2") (pin "10") (pinfunction "PA3_10") (pintype "bidirectional+no_connect"))
    )
    (net (code "48") (name "unconnected-(Y1-E{slash}D-Pad1)") (class "Default")
      (node (ref "Y1") (pin "1") (pinfunction "E/D_1") (pintype "passive+no_connect"))
    )
  )
)
